# REGENIX_Battery_Protection.net
KiCad netlist of a schematic drawn in Altium Designer
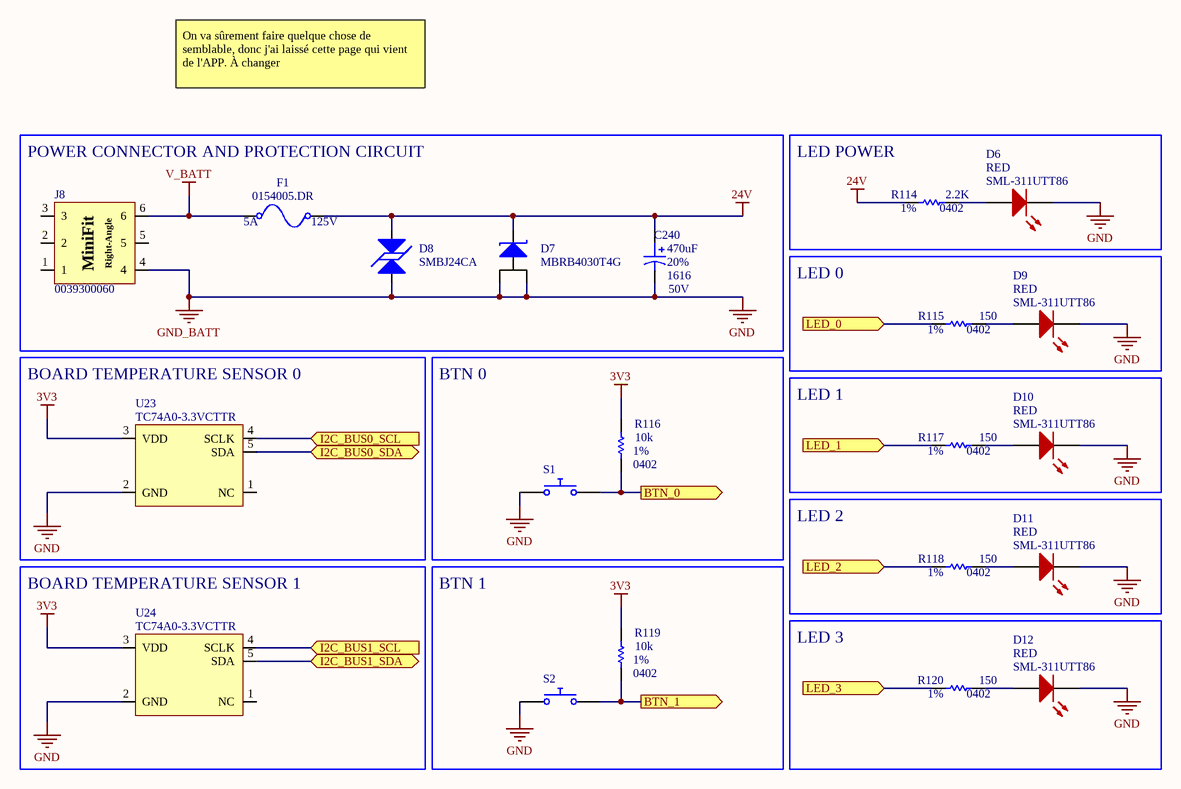
[diagram p0: REGENIX_Battery_Protection.SchDoc]

(export (version "E")
  (design (tool "Eeschema 10.0.6"))
  (components
    (comp (ref "C240")
      (value "470uF")
      (footprint "CAP_ALU_1616_vishay")
      (description "CAP - ALU 470uF 20% 50V - 1616")
      (fields
        (field (name "MFG") "Vishay Dale")
        (field (name "MFG PART NUMBER") "MAL214699108E3")
        (field (name "VOLTAGE") "50V")
        (field (name "PACKAGE") "1616")
        (field (name "PRECISION") "20%")
        (field (name "CREATEDBY") "Jonathan Bouchard")
      )
      (libsource (lib "S7CAS_LIB2023") (part "CAP_ALU_MAL214699108E3"))
    )
    (comp (ref "D6")
      (value "SML-311UTT86")
      (footprint "LED_0603")
      (description "LED - 620nM RED 2mA - 0603")
      (fields
        (field (name "VOLTAGE") "1.8V")
        (field (name "MFG") "ROHM Semiconductor")
        (field (name "ALTIUM_VALUE") "RED")
        (field (name "CREATEDBY") "Jonathan Bouchard")
      )
      (libsource (lib "S7CAS_LIB2023") (part "LED_SML-311UTT86"))
    )
    (comp (ref "D7")
      (value "MBRB4030T4G")
      (footprint "DIO_SCHOTTKY_MBRB4030T4G")
      (description "DIO - 30V MAX 40 A - TO-263-3")
      (fields
        (field (name "CREATEDBY/DATE") "Arnaud Samson - 06/07/18")
        (field (name "VERIFIEDBY") "Jonathan Bouchard 2018-07-12")
      )
      (libsource (lib "S7CAS_LIB2023") (part "DIO_SCHOTTKY_MBRB4030T4G"))
    )
    (comp (ref "D8")
      (value "SMBJ24CA")
      (footprint "TVS_PWR_SMBJ36CA")
      (description "TVS - 24V 26.7V 600W - DO214AA")
      (fields
        (field (name "CREATEDBY/DATE") "Arnaud Samson - 06/07/18")
        (field (name "VERIFIEDBY") "Jonathan Bouchard - 2018-07-13")
      )
      (libsource (lib "S7CAS_LIB2023") (part "TVS_PWR_SMBJ24CA"))
    )
    (comp (ref "D9")
      (value "SML-311UTT86")
      (footprint "LED_0603")
      (description "LED - 620nM RED 2mA - 0603")
      (fields
        (field (name "VOLTAGE") "1.8V")
        (field (name "MFG") "ROHM Semiconductor")
        (field (name "ALTIUM_VALUE") "RED")
        (field (name "CREATEDBY") "Jonathan Bouchard")
      )
      (libsource (lib "S7CAS_LIB2023") (part "LED_SML-311UTT86"))
    )
    (comp (ref "D10")
      (value "SML-311UTT86")
      (footprint "LED_0603")
      (description "LED - 620nM RED 2mA - 0603")
      (fields
        (field (name "VOLTAGE") "1.8V")
        (field (name "MFG") "ROHM Semiconductor")
        (field (name "ALTIUM_VALUE") "RED")
        (field (name "CREATEDBY") "Jonathan Bouchard")
      )
      (libsource (lib "S7CAS_LIB2023") (part "LED_SML-311UTT86"))
    )
    (comp (ref "D11")
      (value "SML-311UTT86")
      (footprint "LED_0603")
      (description "LED - 620nM RED 2mA - 0603")
      (fields
        (field (name "VOLTAGE") "1.8V")
        (field (name "MFG") "ROHM Semiconductor")
        (field (name "ALTIUM_VALUE") "RED")
        (field (name "CREATEDBY") "Jonathan Bouchard")
      )
      (libsource (lib "S7CAS_LIB2023") (part "LED_SML-311UTT86"))
    )
    (comp (ref "D12")
      (value "SML-311UTT86")
      (footprint "LED_0603")
      (description "LED - 620nM RED 2mA - 0603")
      (fields
        (field (name "VOLTAGE") "1.8V")
        (field (name "MFG") "ROHM Semiconductor")
        (field (name "ALTIUM_VALUE") "RED")
        (field (name "CREATEDBY") "Jonathan Bouchard")
      )
      (libsource (lib "S7CAS_LIB2023") (part "LED_SML-311UTT86"))
    )
    (comp (ref "F1")
      (value "0154005.DR")
      (footprint "FUS_0154XXX.DR")
      (description "FUS - 5 A 125 VAC/VDC - 2-SMD")
      (fields
        (field (name "VOLTAGE RATING") "125V")
        (field (name "CURRENT RATING") "5A")
        (field (name "CREATEDBY/DATE") "Arnaud Samson - 06/07/18")
        (field (name "VERIFIEDBY") "Jonathan Bouchard 2018-07-16")
      )
      (libsource (lib "S7CAS_LIB2023") (part "FUS_0154005.DR"))
    )
    (comp (ref "J8")
      (value "0039300060")
      (footprint "CON_MINIFIT_0039300060")
      (description "CON - Mini-Fit Through Hole, Right Angle 6 position")
      (fields
        (field (name "CREATEDBY/DATE") "Joel Lemay 2018-06-21")
        (field (name "VERIFIEDBY") "Caroline Paulin - 10 sept 2018")
      )
      (libsource (lib "S7CAS_LIB2023") (part "CON_MINIFIT_0039300060"))
    )
    (comp (ref "R114")
      (value "2.2K")
      (footprint "RES_0402")
      (description "RES - 0402")
      (fields
        (field (name "VOLTAGE") "50V")
        (field (name "POWER") "1/16W")
        (field (name "PACKAGE") "0402")
        (field (name "PRECISION") "1%")
        (field (name "CREATEDBY") "Jonathan Bouchard")
      )
      (libsource (lib "S7CAS_LIB2023") (part "RES - 0402"))
    )
    (comp (ref "R115")
      (value "150")
      (footprint "RES_0402")
      (description "RES - 0402")
      (fields
        (field (name "VOLTAGE") "50V")
        (field (name "POWER") "1/16W")
        (field (name "PACKAGE") "0402")
        (field (name "PRECISION") "1%")
        (field (name "CREATEDBY") "Jonathan Bouchard")
      )
      (libsource (lib "S7CAS_LIB2023") (part "RES - 0402"))
    )
    (comp (ref "R116")
      (value "10k")
      (footprint "RES_0402")
      (description "RES - 0402")
      (fields
        (field (name "VOLTAGE") "50V")
        (field (name "POWER") "1/16W")
        (field (name "PACKAGE") "0402")
        (field (name "PRECISION") "1%")
        (field (name "CREATEDBY") "Jonathan Bouchard")
      )
      (libsource (lib "S7CAS_LIB2023") (part "RES - 0402"))
    )
    (comp (ref "R117")
      (value "150")
      (footprint "RES_0402")
      (description "RES - 0402")
      (fields
        (field (name "VOLTAGE") "50V")
        (field (name "POWER") "1/16W")
        (field (name "PACKAGE") "0402")
        (field (name "PRECISION") "1%")
        (field (name "CREATEDBY") "Jonathan Bouchard")
      )
      (libsource (lib "S7CAS_LIB2023") (part "RES - 0402"))
    )
    (comp (ref "R118")
      (value "150")
      (footprint "RES_0402")
      (description "RES - 0402")
      (fields
        (field (name "VOLTAGE") "50V")
        (field (name "POWER") "1/16W")
        (field (name "PACKAGE") "0402")
        (field (name "PRECISION") "1%")
        (field (name "CREATEDBY") "Jonathan Bouchard")
      )
      (libsource (lib "S7CAS_LIB2023") (part "RES - 0402"))
    )
    (comp (ref "R119")
      (value "10k")
      (footprint "RES_0402")
      (description "RES - 0402")
      (fields
        (field (name "VOLTAGE") "50V")
        (field (name "POWER") "1/16W")
        (field (name "PACKAGE") "0402")
        (field (name "PRECISION") "1%")
        (field (name "CREATEDBY") "Jonathan Bouchard")
      )
      (libsource (lib "S7CAS_LIB2023") (part "RES - 0402"))
    )
    (comp (ref "R120")
      (value "150")
      (footprint "RES_0402")
      (description "RES - 0402")
      (fields
        (field (name "VOLTAGE") "50V")
        (field (name "POWER") "1/16W")
        (field (name "PACKAGE") "0402")
        (field (name "PRECISION") "1%")
        (field (name "CREATEDBY") "Jonathan Bouchard")
      )
      (libsource (lib "S7CAS_LIB2023") (part "RES - 0402"))
    )
    (comp (ref "S1")
      (value "Push Button Normally Opened")
      (libsource (lib "Simulation Generic Components") (part "Push Button NO"))
    )
    (comp (ref "S2")
      (value "Push Button Normally Opened")
      (libsource (lib "Simulation Generic Components") (part "Push Button NO"))
    )
    (comp (ref "U23")
      (value "TC74A0-3.3VCTTR")
      (footprint "SEN_TEMP_TC74A0-3.3VCTTR")
      (description "SENS - TEMPERATURE SENSOR I2C/SMBUS - SOT23-5")
      (fields
        (field (name "VOLTAGE") "2.7 V ~ 5.5 V")
        (field (name "MFG") "Microchip")
        (field (name "CREATEDBY") "Jonathan Bouchard")
      )
      (libsource (lib "S7CAS_LIB2023") (part "SENS_TEMP_TC74A0-3.3VCTTR"))
    )
    (comp (ref "U24")
      (value "TC74A0-3.3VCTTR")
      (footprint "SEN_TEMP_TC74A0-3.3VCTTR")
      (description "SENS - TEMPERATURE SENSOR I2C/SMBUS - SOT23-5")
      (fields
        (field (name "VOLTAGE") "2.7 V ~ 5.5 V")
        (field (name "MFG") "Microchip")
        (field (name "CREATEDBY") "Jonathan Bouchard")
      )
      (libsource (lib "S7CAS_LIB2023") (part "SENS_TEMP_TC74A0-3.3VCTTR"))
    )
  )
  (nets
    (net (code "1") (name "/BTN_0") (class "Default")
      (node (ref "R116") (pin "1") (pinfunction "1_1") (pintype "passive"))
      (node (ref "S1") (pin "2") (pinfunction "2_2") (pintype "passive"))
    )
    (net (code "2") (name "/BTN_1") (class "Default")
      (node (ref "R119") (pin "1") (pinfunction "1_1") (pintype "passive"))
      (node (ref "S2") (pin "2") (pinfunction "2_2") (pintype "passive"))
    )
    (net (code "3") (name "/I2C_BUS0_SCL") (class "Default")
      (node (ref "U23") (pin "4") (pinfunction "SCLK_4") (pintype "passive"))
    )
    (net (code "4") (name "/I2C_BUS0_SDA") (class "Default")
      (node (ref "U23") (pin "5") (pinfunction "SDA_5") (pintype "passive"))
    )
    (net (code "5") (name "/I2C_BUS1_SCL") (class "Default")
      (node (ref "U24") (pin "4") (pinfunction "SCLK_4") (pintype "passive"))
    )
    (net (code "6") (name "/I2C_BUS1_SDA") (class "Default")
      (node (ref "U24") (pin "5") (pinfunction "SDA_5") (pintype "passive"))
    )
    (net (code "7") (name "/LED_0") (class "Default")
      (node (ref "R115") (pin "2") (pinfunction "2_2") (pintype "passive"))
    )
    (net (code "8") (name "/LED_1") (class "Default")
      (node (ref "R117") (pin "2") (pinfunction "2_2") (pintype "passive"))
    )
    (net (code "9") (name "/LED_2") (class "Default")
      (node (ref "R118") (pin "2") (pinfunction "2_2") (pintype "passive"))
    )
    (net (code "10") (name "/LED_3") (class "Default")
      (node (ref "R120") (pin "2") (pinfunction "2_2") (pintype "passive"))
    )
    (net (code "11") (name "3V3") (class "Default")
      (node (ref "R116") (pin "2") (pinfunction "2_2") (pintype "passive"))
      (node (ref "R119") (pin "2") (pinfunction "2_2") (pintype "passive"))
      (node (ref "U23") (pin "3") (pinfunction "VDD_3") (pintype "passive"))
      (node (ref "U24") (pin "3") (pinfunction "VDD_3") (pintype "passive"))
    )
    (net (code "12") (name "24V") (class "Default")
      (node (ref "C240") (pin "1") (pinfunction "1_1") (pintype "passive"))
      (node (ref "D7") (pin "4") (pinfunction "4_4") (pintype "passive"))
      (node (ref "D8") (pin "1") (pinfunction "1_1") (pintype "passive"))
      (node (ref "F1") (pin "2") (pinfunction "2_2") (pintype "passive"))
      (node (ref "R114") (pin "2") (pinfunction "2_2") (pintype "passive"))
    )
    (net (code "13") (name "GND") (class "Default")
      (node (ref "C240") (pin "2") (pinfunction "2_2") (pintype "passive"))
      (node (ref "D10") (pin "K") (pinfunction "K_K") (pintype "passive"))
      (node (ref "D11") (pin "K") (pinfunction "K_K") (pintype "passive"))
      (node (ref "D12") (pin "K") (pinfunction "K_K") (pintype "passive"))
      (node (ref "D6") (pin "K") (pinfunction "K_K") (pintype "passive"))
      (node (ref "D7") (pin "1") (pinfunction "A_1") (pintype "passive"))
      (node (ref "D7") (pin "3") (pinfunction "3_3") (pintype "passive"))
      (node (ref "D8") (pin "2") (pinfunction "2_2") (pintype "passive"))
      (node (ref "D9") (pin "K") (pinfunction "K_K") (pintype "passive"))
      (node (ref "J8") (pin "4") (pinfunction "4_4") (pintype "passive"))
      (node (ref "S1") (pin "1") (pinfunction "1_1") (pintype "passive"))
      (node (ref "S2") (pin "1") (pinfunction "1_1") (pintype "passive"))
      (node (ref "U23") (pin "2") (pinfunction "GND_2") (pintype "passive"))
      (node (ref "U24") (pin "2") (pinfunction "GND_2") (pintype "passive"))
    )
    (net (code "14") (name "Net-(D6-PadA)") (class "Default")
      (node (ref "D6") (pin "A") (pinfunction "A_A") (pintype "passive"))
      (node (ref "R114") (pin "1") (pinfunction "1_1") (pintype "passive"))
    )
    (net (code "15") (name "Net-(D9-PadA)") (class "Default")
      (node (ref "D9") (pin "A") (pinfunction "A_A") (pintype "passive"))
      (node (ref "R115") (pin "1") (pinfunction "1_1") (pintype "passive"))
    )
    (net (code "16") (name "Net-(D10-PadA)") (class "Default")
      (node (ref "D10") (pin "A") (pinfunction "A_A") (pintype "passive"))
      (node (ref "R117") (pin "1") (pinfunction "1_1") (pintype "passive"))
    )
    (net (code "17") (name "Net-(D11-PadA)") (class "Default")
      (node (ref "D11") (pin "A") (pinfunction "A_A") (pintype "passive"))
      (node (ref "R118") (pin "1") (pinfunction "1_1") (pintype "passive"))
    )
    (net (code "18") (name "Net-(D12-PadA)") (class "Default")
      (node (ref "D12") (pin "A") (pinfunction "A_A") (pintype "passive"))
      (node (ref "R120") (pin "1") (pinfunction "1_1") (pintype "passive"))
    )
    (net (code "19") (name "V_BATT") (class "Default")
      (node (ref "F1") (pin "1") (pinfunction "1_1") (pintype "passive"))
      (node (ref "J8") (pin "6") (pinfunction "6_6") (pintype "passive"))
    )
    (net (code "20") (name "unconnected-(J8-Pad1)") (class "Default")
      (node (ref "J8") (pin "1") (pinfunction "1_1") (pintype "passive"))
    )
    (net (code "21") (name "unconnected-(J8-Pad2)") (class "Default")
      (node (ref "J8") (pin "2") (pinfunction "2_2") (pintype "passive"))
    )
    (net (code "22") (name "unconnected-(J8-Pad3)") (class "Default")
      (node (ref "J8") (pin "3") (pinfunction "3_3") (pintype "passive"))
    )
    (net (code "23") (name "unconnected-(J8-Pad5)") (class "Default")
      (node (ref "J8") (pin "5") (pinfunction "5_5") (pintype "passive"))
    )
    (net (code "24") (name "unconnected-(U23-NC-Pad1)") (class "Default")
      (node (ref "U23") (pin "1") (pinfunction "NC_1") (pintype "passive"))
    )
    (net (code "25") (name "unconnected-(U24-NC-Pad1)") (class "Default")
      (node (ref "U24") (pin "1") (pinfunction "NC_1") (pintype "passive"))
    )
  )
)
